# Array.net
KiCad netlist of a schematic drawn in Altium Designer
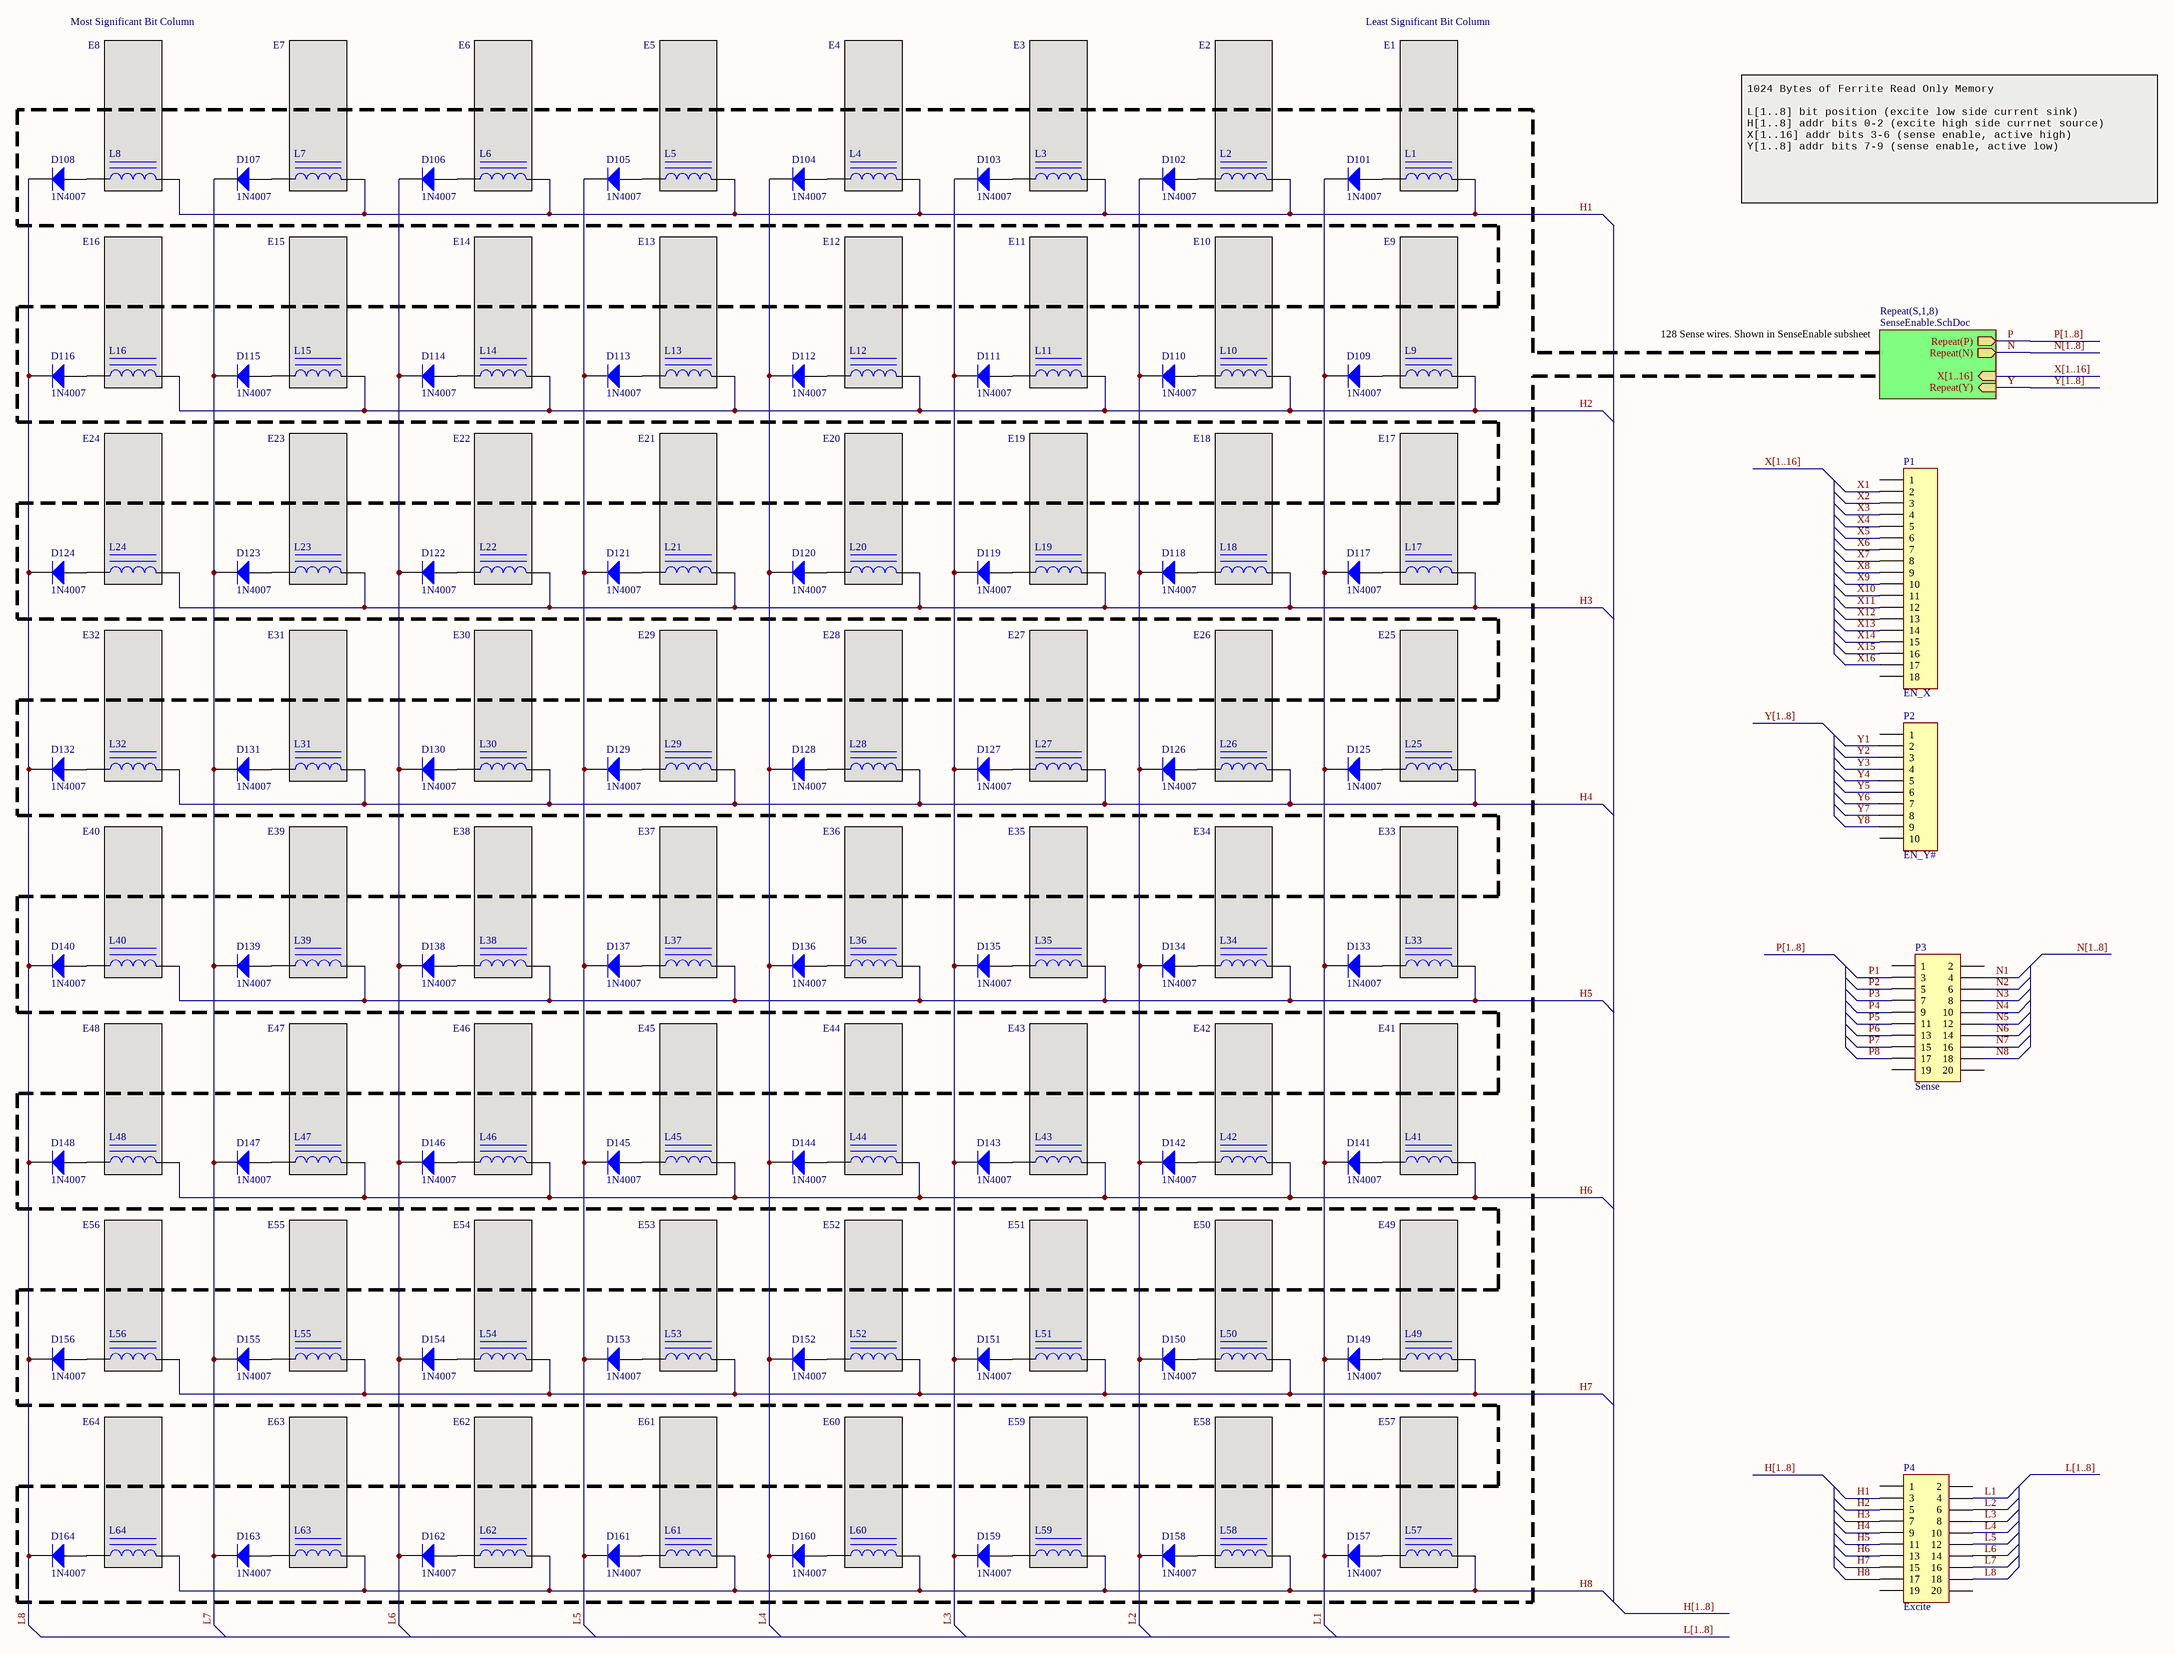
[diagram p0: Array.SchDoc]

(export (version "E")
  (design (tool "Eeschema 10.0.6"))
  (components
    (comp (ref "D101")
      (value "1N4007")
      (footprint "DO-41")
      (description "1 Amp General Purpose Rectifier")
      (fields (field (name "PUBLISHER") "Altium Limited"))
      (libsource (lib "Miscellaneous Devices") (part "Diode 1N4007"))
    )
    (comp (ref "D102")
      (value "1N4007")
      (footprint "DO-41")
      (description "1 Amp General Purpose Rectifier")
      (fields (field (name "PUBLISHER") "Altium Limited"))
      (libsource (lib "Miscellaneous Devices") (part "Diode 1N4007"))
    )
    (comp (ref "D103")
      (value "1N4007")
      (footprint "DO-41")
      (description "1 Amp General Purpose Rectifier")
      (fields (field (name "PUBLISHER") "Altium Limited"))
      (libsource (lib "Miscellaneous Devices") (part "Diode 1N4007"))
    )
    (comp (ref "D104")
      (value "1N4007")
      (footprint "DO-41")
      (description "1 Amp General Purpose Rectifier")
      (fields (field (name "PUBLISHER") "Altium Limited"))
      (libsource (lib "Miscellaneous Devices") (part "Diode 1N4007"))
    )
    (comp (ref "D105")
      (value "1N4007")
      (footprint "DO-41")
      (description "1 Amp General Purpose Rectifier")
      (fields (field (name "PUBLISHER") "Altium Limited"))
      (libsource (lib "Miscellaneous Devices") (part "Diode 1N4007"))
    )
    (comp (ref "D106")
      (value "1N4007")
      (footprint "DO-41")
      (description "1 Amp General Purpose Rectifier")
      (fields (field (name "PUBLISHER") "Altium Limited"))
      (libsource (lib "Miscellaneous Devices") (part "Diode 1N4007"))
    )
    (comp (ref "D107")
      (value "1N4007")
      (footprint "DO-41")
      (description "1 Amp General Purpose Rectifier")
      (fields (field (name "PUBLISHER") "Altium Limited"))
      (libsource (lib "Miscellaneous Devices") (part "Diode 1N4007"))
    )
    (comp (ref "D108")
      (value "1N4007")
      (footprint "DO-41")
      (description "1 Amp General Purpose Rectifier")
      (fields (field (name "PUBLISHER") "Altium Limited"))
      (libsource (lib "Miscellaneous Devices") (part "Diode 1N4007"))
    )
    (comp (ref "D109")
      (value "1N4007")
      (footprint "DO-41")
      (description "1 Amp General Purpose Rectifier")
      (fields (field (name "PUBLISHER") "Altium Limited"))
      (libsource (lib "Miscellaneous Devices") (part "Diode 1N4007"))
    )
    (comp (ref "D110")
      (value "1N4007")
      (footprint "DO-41")
      (description "1 Amp General Purpose Rectifier")
      (fields (field (name "PUBLISHER") "Altium Limited"))
      (libsource (lib "Miscellaneous Devices") (part "Diode 1N4007"))
    )
    (comp (ref "D111")
      (value "1N4007")
      (footprint "DO-41")
      (description "1 Amp General Purpose Rectifier")
      (fields (field (name "PUBLISHER") "Altium Limited"))
      (libsource (lib "Miscellaneous Devices") (part "Diode 1N4007"))
    )
    (comp (ref "D112")
      (value "1N4007")
      (footprint "DO-41")
      (description "1 Amp General Purpose Rectifier")
      (fields (field (name "PUBLISHER") "Altium Limited"))
      (libsource (lib "Miscellaneous Devices") (part "Diode 1N4007"))
    )
    (comp (ref "D113")
      (value "1N4007")
      (footprint "DO-41")
      (description "1 Amp General Purpose Rectifier")
      (fields (field (name "PUBLISHER") "Altium Limited"))
      (libsource (lib "Miscellaneous Devices") (part "Diode 1N4007"))
    )
    (comp (ref "D114")
      (value "1N4007")
      (footprint "DO-41")
      (description "1 Amp General Purpose Rectifier")
      (fields (field (name "PUBLISHER") "Altium Limited"))
      (libsource (lib "Miscellaneous Devices") (part "Diode 1N4007"))
    )
    (comp (ref "D115")
      (value "1N4007")
      (footprint "DO-41")
      (description "1 Amp General Purpose Rectifier")
      (fields (field (name "PUBLISHER") "Altium Limited"))
      (libsource (lib "Miscellaneous Devices") (part "Diode 1N4007"))
    )
    (comp (ref "D116")
      (value "1N4007")
      (footprint "DO-41")
      (description "1 Amp General Purpose Rectifier")
      (fields (field (name "PUBLISHER") "Altium Limited"))
      (libsource (lib "Miscellaneous Devices") (part "Diode 1N4007"))
    )
    (comp (ref "D117")
      (value "1N4007")
      (footprint "DO-41")
      (description "1 Amp General Purpose Rectifier")
      (fields (field (name "PUBLISHER") "Altium Limited"))
      (libsource (lib "Miscellaneous Devices") (part "Diode 1N4007"))
    )
    (comp (ref "D118")
      (value "1N4007")
      (footprint "DO-41")
      (description "1 Amp General Purpose Rectifier")
      (fields (field (name "PUBLISHER") "Altium Limited"))
      (libsource (lib "Miscellaneous Devices") (part "Diode 1N4007"))
    )
    (comp (ref "D119")
      (value "1N4007")
      (footprint "DO-41")
      (description "1 Amp General Purpose Rectifier")
      (fields (field (name "PUBLISHER") "Altium Limited"))
      (libsource (lib "Miscellaneous Devices") (part "Diode 1N4007"))
    )
    (comp (ref "D120")
      (value "1N4007")
      (footprint "DO-41")
      (description "1 Amp General Purpose Rectifier")
      (fields (field (name "PUBLISHER") "Altium Limited"))
      (libsource (lib "Miscellaneous Devices") (part "Diode 1N4007"))
    )
    (comp (ref "D121")
      (value "1N4007")
      (footprint "DO-41")
      (description "1 Amp General Purpose Rectifier")
      (fields (field (name "PUBLISHER") "Altium Limited"))
      (libsource (lib "Miscellaneous Devices") (part "Diode 1N4007"))
    )
    (comp (ref "D122")
      (value "1N4007")
      (footprint "DO-41")
      (description "1 Amp General Purpose Rectifier")
      (fields (field (name "PUBLISHER") "Altium Limited"))
      (libsource (lib "Miscellaneous Devices") (part "Diode 1N4007"))
    )
    (comp (ref "D123")
      (value "1N4007")
      (footprint "DO-41")
      (description "1 Amp General Purpose Rectifier")
      (fields (field (name "PUBLISHER") "Altium Limited"))
      (libsource (lib "Miscellaneous Devices") (part "Diode 1N4007"))
    )
    (comp (ref "D124")
      (value "1N4007")
      (footprint "DO-41")
      (description "1 Amp General Purpose Rectifier")
      (fields (field (name "PUBLISHER") "Altium Limited"))
      (libsource (lib "Miscellaneous Devices") (part "Diode 1N4007"))
    )
    (comp (ref "D125")
      (value "1N4007")
      (footprint "DO-41")
      (description "1 Amp General Purpose Rectifier")
      (fields (field (name "PUBLISHER") "Altium Limited"))
      (libsource (lib "Miscellaneous Devices") (part "Diode 1N4007"))
    )
    (comp (ref "D126")
      (value "1N4007")
      (footprint "DO-41")
      (description "1 Amp General Purpose Rectifier")
      (fields (field (name "PUBLISHER") "Altium Limited"))
      (libsource (lib "Miscellaneous Devices") (part "Diode 1N4007"))
    )
    (comp (ref "D127")
      (value "1N4007")
      (footprint "DO-41")
      (description "1 Amp General Purpose Rectifier")
      (fields (field (name "PUBLISHER") "Altium Limited"))
      (libsource (lib "Miscellaneous Devices") (part "Diode 1N4007"))
    )
    (comp (ref "D128")
      (value "1N4007")
      (footprint "DO-41")
      (description "1 Amp General Purpose Rectifier")
      (fields (field (name "PUBLISHER") "Altium Limited"))
      (libsource (lib "Miscellaneous Devices") (part "Diode 1N4007"))
    )
    (comp (ref "D129")
      (value "1N4007")
      (footprint "DO-41")
      (description "1 Amp General Purpose Rectifier")
      (fields (field (name "PUBLISHER") "Altium Limited"))
      (libsource (lib "Miscellaneous Devices") (part "Diode 1N4007"))
    )
    (comp (ref "D130")
      (value "1N4007")
      (footprint "DO-41")
      (description "1 Amp General Purpose Rectifier")
      (fields (field (name "PUBLISHER") "Altium Limited"))
      (libsource (lib "Miscellaneous Devices") (part "Diode 1N4007"))
    )
    (comp (ref "D131")
      (value "1N4007")
      (footprint "DO-41")
      (description "1 Amp General Purpose Rectifier")
      (fields (field (name "PUBLISHER") "Altium Limited"))
      (libsource (lib "Miscellaneous Devices") (part "Diode 1N4007"))
    )
    (comp (ref "D132")
      (value "1N4007")
      (footprint "DO-41")
      (description "1 Amp General Purpose Rectifier")
      (fields (field (name "PUBLISHER") "Altium Limited"))
      (libsource (lib "Miscellaneous Devices") (part "Diode 1N4007"))
    )
    (comp (ref "D133")
      (value "1N4007")
      (footprint "DO-41")
      (description "1 Amp General Purpose Rectifier")
      (fields (field (name "PUBLISHER") "Altium Limited"))
      (libsource (lib "Miscellaneous Devices") (part "Diode 1N4007"))
    )
    (comp (ref "D134")
      (value "1N4007")
      (footprint "DO-41")
      (description "1 Amp General Purpose Rectifier")
      (fields (field (name "PUBLISHER") "Altium Limited"))
      (libsource (lib "Miscellaneous Devices") (part "Diode 1N4007"))
    )
    (comp (ref "D135")
      (value "1N4007")
      (footprint "DO-41")
      (description "1 Amp General Purpose Rectifier")
      (fields (field (name "PUBLISHER") "Altium Limited"))
      (libsource (lib "Miscellaneous Devices") (part "Diode 1N4007"))
    )
    (comp (ref "D136")
      (value "1N4007")
      (footprint "DO-41")
      (description "1 Amp General Purpose Rectifier")
      (fields (field (name "PUBLISHER") "Altium Limited"))
      (libsource (lib "Miscellaneous Devices") (part "Diode 1N4007"))
    )
    (comp (ref "D137")
      (value "1N4007")
      (footprint "DO-41")
      (description "1 Amp General Purpose Rectifier")
      (fields (field (name "PUBLISHER") "Altium Limited"))
      (libsource (lib "Miscellaneous Devices") (part "Diode 1N4007"))
    )
    (comp (ref "D138")
      (value "1N4007")
      (footprint "DO-41")
      (description "1 Amp General Purpose Rectifier")
      (fields (field (name "PUBLISHER") "Altium Limited"))
      (libsource (lib "Miscellaneous Devices") (part "Diode 1N4007"))
    )
    (comp (ref "D139")
      (value "1N4007")
      (footprint "DO-41")
      (description "1 Amp General Purpose Rectifier")
      (fields (field (name "PUBLISHER") "Altium Limited"))
      (libsource (lib "Miscellaneous Devices") (part "Diode 1N4007"))
    )
    (comp (ref "D140")
      (value "1N4007")
      (footprint "DO-41")
      (description "1 Amp General Purpose Rectifier")
      (fields (field (name "PUBLISHER") "Altium Limited"))
      (libsource (lib "Miscellaneous Devices") (part "Diode 1N4007"))
    )
    (comp (ref "D141")
      (value "1N4007")
      (footprint "DO-41")
      (description "1 Amp General Purpose Rectifier")
      (fields (field (name "PUBLISHER") "Altium Limited"))
      (libsource (lib "Miscellaneous Devices") (part "Diode 1N4007"))
    )
    (comp (ref "D142")
      (value "1N4007")
      (footprint "DO-41")
      (description "1 Amp General Purpose Rectifier")
      (fields (field (name "PUBLISHER") "Altium Limited"))
      (libsource (lib "Miscellaneous Devices") (part "Diode 1N4007"))
    )
    (comp (ref "D143")
      (value "1N4007")
      (footprint "DO-41")
      (description "1 Amp General Purpose Rectifier")
      (fields (field (name "PUBLISHER") "Altium Limited"))
      (libsource (lib "Miscellaneous Devices") (part "Diode 1N4007"))
    )
    (comp (ref "D144")
      (value "1N4007")
      (footprint "DO-41")
      (description "1 Amp General Purpose Rectifier")
      (fields (field (name "PUBLISHER") "Altium Limited"))
      (libsource (lib "Miscellaneous Devices") (part "Diode 1N4007"))
    )
    (comp (ref "D145")
      (value "1N4007")
      (footprint "DO-41")
      (description "1 Amp General Purpose Rectifier")
      (fields (field (name "PUBLISHER") "Altium Limited"))
      (libsource (lib "Miscellaneous Devices") (part "Diode 1N4007"))
    )
    (comp (ref "D146")
      (value "1N4007")
      (footprint "DO-41")
      (description "1 Amp General Purpose Rectifier")
      (fields (field (name "PUBLISHER") "Altium Limited"))
      (libsource (lib "Miscellaneous Devices") (part "Diode 1N4007"))
    )
    (comp (ref "D147")
      (value "1N4007")
      (footprint "DO-41")
      (description "1 Amp General Purpose Rectifier")
      (fields (field (name "PUBLISHER") "Altium Limited"))
      (libsource (lib "Miscellaneous Devices") (part "Diode 1N4007"))
    )
    (comp (ref "D148")
      (value "1N4007")
      (footprint "DO-41")
      (description "1 Amp General Purpose Rectifier")
      (fields (field (name "PUBLISHER") "Altium Limited"))
      (libsource (lib "Miscellaneous Devices") (part "Diode 1N4007"))
    )
    (comp (ref "D149")
      (value "1N4007")
      (footprint "DO-41")
      (description "1 Amp General Purpose Rectifier")
      (fields (field (name "PUBLISHER") "Altium Limited"))
      (libsource (lib "Miscellaneous Devices") (part "Diode 1N4007"))
    )
    (comp (ref "D150")
      (value "1N4007")
      (footprint "DO-41")
      (description "1 Amp General Purpose Rectifier")
      (fields (field (name "PUBLISHER") "Altium Limited"))
      (libsource (lib "Miscellaneous Devices") (part "Diode 1N4007"))
    )
    (comp (ref "D151")
      (value "1N4007")
      (footprint "DO-41")
      (description "1 Amp General Purpose Rectifier")
      (fields (field (name "PUBLISHER") "Altium Limited"))
      (libsource (lib "Miscellaneous Devices") (part "Diode 1N4007"))
    )
    (comp (ref "D152")
      (value "1N4007")
      (footprint "DO-41")
      (description "1 Amp General Purpose Rectifier")
      (fields (field (name "PUBLISHER") "Altium Limited"))
      (libsource (lib "Miscellaneous Devices") (part "Diode 1N4007"))
    )
    (comp (ref "D153")
      (value "1N4007")
      (footprint "DO-41")
      (description "1 Amp General Purpose Rectifier")
      (fields (field (name "PUBLISHER") "Altium Limited"))
      (libsource (lib "Miscellaneous Devices") (part "Diode 1N4007"))
    )
    (comp (ref "D154")
      (value "1N4007")
      (footprint "DO-41")
      (description "1 Amp General Purpose Rectifier")
      (fields (field (name "PUBLISHER") "Altium Limited"))
      (libsource (lib "Miscellaneous Devices") (part "Diode 1N4007"))
    )
    (comp (ref "D155")
      (value "1N4007")
      (footprint "DO-41")
      (description "1 Amp General Purpose Rectifier")
      (fields (field (name "PUBLISHER") "Altium Limited"))
      (libsource (lib "Miscellaneous Devices") (part "Diode 1N4007"))
    )
    (comp (ref "D156")
      (value "1N4007")
      (footprint "DO-41")
      (description "1 Amp General Purpose Rectifier")
      (fields (field (name "PUBLISHER") "Altium Limited"))
      (libsource (lib "Miscellaneous Devices") (part "Diode 1N4007"))
    )
    (comp (ref "D157")
      (value "1N4007")
      (footprint "DO-41")
      (description "1 Amp General Purpose Rectifier")
      (fields (field (name "PUBLISHER") "Altium Limited"))
      (libsource (lib "Miscellaneous Devices") (part "Diode 1N4007"))
    )
    (comp (ref "D158")
      (value "1N4007")
      (footprint "DO-41")
      (description "1 Amp General Purpose Rectifier")
      (fields (field (name "PUBLISHER") "Altium Limited"))
      (libsource (lib "Miscellaneous Devices") (part "Diode 1N4007"))
    )
    (comp (ref "D159")
      (value "1N4007")
      (footprint "DO-41")
      (description "1 Amp General Purpose Rectifier")
      (fields (field (name "PUBLISHER") "Altium Limited"))
      (libsource (lib "Miscellaneous Devices") (part "Diode 1N4007"))
    )
    (comp (ref "D160")
      (value "1N4007")
      (footprint "DO-41")
      (description "1 Amp General Purpose Rectifier")
      (fields (field (name "PUBLISHER") "Altium Limited"))
      (libsource (lib "Miscellaneous Devices") (part "Diode 1N4007"))
    )
    (comp (ref "D161")
      (value "1N4007")
      (footprint "DO-41")
      (description "1 Amp General Purpose Rectifier")
      (fields (field (name "PUBLISHER") "Altium Limited"))
      (libsource (lib "Miscellaneous Devices") (part "Diode 1N4007"))
    )
    (comp (ref "D162")
      (value "1N4007")
      (footprint "DO-41")
      (description "1 Amp General Purpose Rectifier")
      (fields (field (name "PUBLISHER") "Altium Limited"))
      (libsource (lib "Miscellaneous Devices") (part "Diode 1N4007"))
    )
    (comp (ref "D163")
      (value "1N4007")
      (footprint "DO-41")
      (description "1 Amp General Purpose Rectifier")
      (fields (field (name "PUBLISHER") "Altium Limited"))
      (libsource (lib "Miscellaneous Devices") (part "Diode 1N4007"))
    )
    (comp (ref "D164")
      (value "1N4007")
      (footprint "DO-41")
      (description "1 Amp General Purpose Rectifier")
      (fields (field (name "PUBLISHER") "Altium Limited"))
      (libsource (lib "Miscellaneous Devices") (part "Diode 1N4007"))
    )
    (comp (ref "L1")
      (value "Inductor Iron")
      (footprint "AXIAL-0.9")
      (description "Magnetic-Core Inductor")
      (fields (field (name "PUBLISHER") "Altium Limited"))
      (libsource (lib "Miscellaneous Devices") (part "Inductor Iron"))
    )
    (comp (ref "L2")
      (value "Inductor Iron")
      (footprint "AXIAL-0.9")
      (description "Magnetic-Core Inductor")
      (fields (field (name "PUBLISHER") "Altium Limited"))
      (libsource (lib "Miscellaneous Devices") (part "Inductor Iron"))
    )
    (comp (ref "L3")
      (value "Inductor Iron")
      (footprint "AXIAL-0.9")
      (description "Magnetic-Core Inductor")
      (fields (field (name "PUBLISHER") "Altium Limited"))
      (libsource (lib "Miscellaneous Devices") (part "Inductor Iron"))
    )
    (comp (ref "L4")
      (value "Inductor Iron")
      (footprint "AXIAL-0.9")
      (description "Magnetic-Core Inductor")
      (fields (field (name "PUBLISHER") "Altium Limited"))
      (libsource (lib "Miscellaneous Devices") (part "Inductor Iron"))
    )
    (comp (ref "L5")
      (value "Inductor Iron")
      (footprint "AXIAL-0.9")
      (description "Magnetic-Core Inductor")
      (fields (field (name "PUBLISHER") "Altium Limited"))
      (libsource (lib "Miscellaneous Devices") (part "Inductor Iron"))
    )
    (comp (ref "L6")
      (value "Inductor Iron")
      (footprint "AXIAL-0.9")
      (description "Magnetic-Core Inductor")
      (fields (field (name "PUBLISHER") "Altium Limited"))
      (libsource (lib "Miscellaneous Devices") (part "Inductor Iron"))
    )
    (comp (ref "L7")
      (value "Inductor Iron")
      (footprint "AXIAL-0.9")
      (description "Magnetic-Core Inductor")
      (fields (field (name "PUBLISHER") "Altium Limited"))
      (libsource (lib "Miscellaneous Devices") (part "Inductor Iron"))
    )
    (comp (ref "L8")
      (value "Inductor Iron")
      (footprint "AXIAL-0.9")
      (description "Magnetic-Core Inductor")
      (fields (field (name "PUBLISHER") "Altium Limited"))
      (libsource (lib "Miscellaneous Devices") (part "Inductor Iron"))
    )
    (comp (ref "L9")
      (value "Inductor Iron")
      (footprint "AXIAL-0.9")
      (description "Magnetic-Core Inductor")
      (fields (field (name "PUBLISHER") "Altium Limited"))
      (libsource (lib "Miscellaneous Devices") (part "Inductor Iron"))
    )
    (comp (ref "L10")
      (value "Inductor Iron")
      (footprint "AXIAL-0.9")
      (description "Magnetic-Core Inductor")
      (fields (field (name "PUBLISHER") "Altium Limited"))
      (libsource (lib "Miscellaneous Devices") (part "Inductor Iron"))
    )
    (comp (ref "L11")
      (value "Inductor Iron")
      (footprint "AXIAL-0.9")
      (description "Magnetic-Core Inductor")
      (fields (field (name "PUBLISHER") "Altium Limited"))
      (libsource (lib "Miscellaneous Devices") (part "Inductor Iron"))
    )
    (comp (ref "L12")
      (value "Inductor Iron")
      (footprint "AXIAL-0.9")
      (description "Magnetic-Core Inductor")
      (fields (field (name "PUBLISHER") "Altium Limited"))
      (libsource (lib "Miscellaneous Devices") (part "Inductor Iron"))
    )
    (comp (ref "L13")
      (value "Inductor Iron")
      (footprint "AXIAL-0.9")
      (description "Magnetic-Core Inductor")
      (fields (field (name "PUBLISHER") "Altium Limited"))
      (libsource (lib "Miscellaneous Devices") (part "Inductor Iron"))
    )
    (comp (ref "L14")
      (value "Inductor Iron")
      (footprint "AXIAL-0.9")
      (description "Magnetic-Core Inductor")
      (fields (field (name "PUBLISHER") "Altium Limited"))
      (libsource (lib "Miscellaneous Devices") (part "Inductor Iron"))
    )
    (comp (ref "L15")
      (value "Inductor Iron")
      (footprint "AXIAL-0.9")
      (description "Magnetic-Core Inductor")
      (fields (field (name "PUBLISHER") "Altium Limited"))
      (libsource (lib "Miscellaneous Devices") (part "Inductor Iron"))
    )
    (comp (ref "L16")
      (value "Inductor Iron")
      (footprint "AXIAL-0.9")
      (description "Magnetic-Core Inductor")
      (fields (field (name "PUBLISHER") "Altium Limited"))
      (libsource (lib "Miscellaneous Devices") (part "Inductor Iron"))
    )
    (comp (ref "L17")
      (value "Inductor Iron")
      (footprint "AXIAL-0.9")
      (description "Magnetic-Core Inductor")
      (fields (field (name "PUBLISHER") "Altium Limited"))
      (libsource (lib "Miscellaneous Devices") (part "Inductor Iron"))
    )
    (comp (ref "L18")
      (value "Inductor Iron")
      (footprint "AXIAL-0.9")
      (description "Magnetic-Core Inductor")
      (fields (field (name "PUBLISHER") "Altium Limited"))
      (libsource (lib "Miscellaneous Devices") (part "Inductor Iron"))
    )
    (comp (ref "L19")
      (value "Inductor Iron")
      (footprint "AXIAL-0.9")
      (description "Magnetic-Core Inductor")
      (fields (field (name "PUBLISHER") "Altium Limited"))
      (libsource (lib "Miscellaneous Devices") (part "Inductor Iron"))
    )
    (comp (ref "L20")
      (value "Inductor Iron")
      (footprint "AXIAL-0.9")
      (description "Magnetic-Core Inductor")
      (fields (field (name "PUBLISHER") "Altium Limited"))
      (libsource (lib "Miscellaneous Devices") (part "Inductor Iron"))
    )
    (comp (ref "L21")
      (value "Inductor Iron")
      (footprint "AXIAL-0.9")
      (description "Magnetic-Core Inductor")
      (fields (field (name "PUBLISHER") "Altium Limited"))
      (libsource (lib "Miscellaneous Devices") (part "Inductor Iron"))
    )
    (comp (ref "L22")
      (value "Inductor Iron")
      (footprint "AXIAL-0.9")
      (description "Magnetic-Core Inductor")
      (fields (field (name "PUBLISHER") "Altium Limited"))
      (libsource (lib "Miscellaneous Devices") (part "Inductor Iron"))
    )
    (comp (ref "L23")
      (value "Inductor Iron")
      (footprint "AXIAL-0.9")
      (description "Magnetic-Core Inductor")
      (fields (field (name "PUBLISHER") "Altium Limited"))
      (libsource (lib "Miscellaneous Devices") (part "Inductor Iron"))
    )
    (comp (ref "L24")
      (value "Inductor Iron")
      (footprint "AXIAL-0.9")
      (description "Magnetic-Core Inductor")
      (fields (field (name "PUBLISHER") "Altium Limited"))
      (libsource (lib "Miscellaneous Devices") (part "Inductor Iron"))
    )
    (comp (ref "L25")
      (value "Inductor Iron")
      (footprint "AXIAL-0.9")
      (description "Magnetic-Core Inductor")
      (fields (field (name "PUBLISHER") "Altium Limited"))
      (libsource (lib "Miscellaneous Devices") (part "Inductor Iron"))
    )
    (comp (ref "L26")
      (value "Inductor Iron")
      (footprint "AXIAL-0.9")
      (description "Magnetic-Core Inductor")
      (fields (field (name "PUBLISHER") "Altium Limited"))
      (libsource (lib "Miscellaneous Devices") (part "Inductor Iron"))
    )
    (comp (ref "L27")
      (value "Inductor Iron")
      (footprint "AXIAL-0.9")
      (description "Magnetic-Core Inductor")
      (fields (field (name "PUBLISHER") "Altium Limited"))
      (libsource (lib "Miscellaneous Devices") (part "Inductor Iron"))
    )
    (comp (ref "L28")
      (value "Inductor Iron")
      (footprint "AXIAL-0.9")
      (description "Magnetic-Core Inductor")
      (fields (field (name "PUBLISHER") "Altium Limited"))
      (libsource (lib "Miscellaneous Devices") (part "Inductor Iron"))
    )
    (comp (ref "L29")
      (value "Inductor Iron")
      (footprint "AXIAL-0.9")
      (description "Magnetic-Core Inductor")
      (fields (field (name "PUBLISHER") "Altium Limited"))
      (libsource (lib "Miscellaneous Devices") (part "Inductor Iron"))
    )
    (comp (ref "L30")
      (value "Inductor Iron")
      (footprint "AXIAL-0.9")
      (description "Magnetic-Core Inductor")
      (fields (field (name "PUBLISHER") "Altium Limited"))
      (libsource (lib "Miscellaneous Devices") (part "Inductor Iron"))
    )
    (comp (ref "L31")
      (value "Inductor Iron")
      (footprint "AXIAL-0.9")
      (description "Magnetic-Core Inductor")
      (fields (field (name "PUBLISHER") "Altium Limited"))
      (libsource (lib "Miscellaneous Devices") (part "Inductor Iron"))
    )
    (comp (ref "L32")
      (value "Inductor Iron")
      (footprint "AXIAL-0.9")
      (description "Magnetic-Core Inductor")
      (fields (field (name "PUBLISHER") "Altium Limited"))
      (libsource (lib "Miscellaneous Devices") (part "Inductor Iron"))
    )
    (comp (ref "L33")
      (value "Inductor Iron")
      (footprint "AXIAL-0.9")
      (description "Magnetic-Core Inductor")
      (fields (field (name "PUBLISHER") "Altium Limited"))
      (libsource (lib "Miscellaneous Devices") (part "Inductor Iron"))
    )
    (comp (ref "L34")
      (value "Inductor Iron")
      (footprint "AXIAL-0.9")
      (description "Magnetic-Core Inductor")
      (fields (field (name "PUBLISHER") "Altium Limited"))
      (libsource (lib "Miscellaneous Devices") (part "Inductor Iron"))
    )
    (comp (ref "L35")
      (value "Inductor Iron")
      (footprint "AXIAL-0.9")
      (description "Magnetic-Core Inductor")
      (fields (field (name "PUBLISHER") "Altium Limited"))
      (libsource (lib "Miscellaneous Devices") (part "Inductor Iron"))
    )
    (comp (ref "L36")
      (value "Inductor Iron")
      (footprint "AXIAL-0.9")
      (description "Magnetic-Core Inductor")
      (fields (field (name "PUBLISHER") "Altium Limited"))
      (libsource (lib "Miscellaneous Devices") (part "Inductor Iron"))
    )
    (comp (ref "L37")
      (value "Inductor Iron")
      (footprint "AXIAL-0.9")
      (description "Magnetic-Core Inductor")
      (fields (field (name "PUBLISHER") "Altium Limited"))
      (libsource (lib "Miscellaneous Devices") (part "Inductor Iron"))
    )
    (comp (ref "L38")
      (value "Inductor Iron")
      (footprint "AXIAL-0.9")
      (description "Magnetic-Core Inductor")
      (fields (field (name "PUBLISHER") "Altium Limited"))
      (libsource (lib "Miscellaneous Devices") (part "Inductor Iron"))
    )
    (comp (ref "L39")
      (value "Inductor Iron")
      (footprint "AXIAL-0.9")
      (description "Magnetic-Core Inductor")
      (fields (field (name "PUBLISHER") "Altium Limited"))
      (libsource (lib "Miscellaneous Devices") (part "Inductor Iron"))
    )
    (comp (ref "L40")
      (value "Inductor Iron")
      (footprint "AXIAL-0.9")
      (description "Magnetic-Core Inductor")
      (fields (field (name "PUBLISHER") "Altium Limited"))
      (libsource (lib "Miscellaneous Devices") (part "Inductor Iron"))
    )
    (comp (ref "L41")
      (value "Inductor Iron")
      (footprint "AXIAL-0.9")
      (description "Magnetic-Core Inductor")
      (fields (field (name "PUBLISHER") "Altium Limited"))
      (libsource (lib "Miscellaneous Devices") (part "Inductor Iron"))
    )
    (comp (ref "L42")
      (value "Inductor Iron")
      (footprint "AXIAL-0.9")
      (description "Magnetic-Core Inductor")
      (fields (field (name "PUBLISHER") "Altium Limited"))
      (libsource (lib "Miscellaneous Devices") (part "Inductor Iron"))
    )
    (comp (ref "L43")
      (value "Inductor Iron")
      (footprint "AXIAL-0.9")
      (description "Magnetic-Core Inductor")
      (fields (field (name "PUBLISHER") "Altium Limited"))
      (libsource (lib "Miscellaneous Devices") (part "Inductor Iron"))
    )
    (comp (ref "L44")
      (value "Inductor Iron")
      (footprint "AXIAL-0.9")
      (description "Magnetic-Core Inductor")
      (fields (field (name "PUBLISHER") "Altium Limited"))
      (libsource (lib "Miscellaneous Devices") (part "Inductor Iron"))
    )
    (comp (ref "L45")
      (value "Inductor Iron")
      (footprint "AXIAL-0.9")
      (description "Magnetic-Core Inductor")
      (fields (field (name "PUBLISHER") "Altium Limited"))
      (libsource (lib "Miscellaneous Devices") (part "Inductor Iron"))
    )
    (comp (ref "L46")
      (value "Inductor Iron")
      (footprint "AXIAL-0.9")
      (description "Magnetic-Core Inductor")
      (fields (field (name "PUBLISHER") "Altium Limited"))
      (libsource (lib "Miscellaneous Devices") (part "Inductor Iron"))
    )
    (comp (ref "L47")
      (value "Inductor Iron")
      (footprint "AXIAL-0.9")
      (description "Magnetic-Core Inductor")
      (fields (field (name "PUBLISHER") "Altium Limited"))
      (libsource (lib "Miscellaneous Devices") (part "Inductor Iron"))
    )
    (comp (ref "L48")
      (value "Inductor Iron")
      (footprint "AXIAL-0.9")
      (description "Magnetic-Core Inductor")
      (fields (field (name "PUBLISHER") "Altium Limited"))
      (libsource (lib "Miscellaneous Devices") (part "Inductor Iron"))
    )
    (comp (ref "L49")
      (value "Inductor Iron")
      (footprint "AXIAL-0.9")
      (description "Magnetic-Core Inductor")
      (fields (field (name "PUBLISHER") "Altium Limited"))
      (libsource (lib "Miscellaneous Devices") (part "Inductor Iron"))
    )
    (comp (ref "L50")
      (value "Inductor Iron")
      (footprint "AXIAL-0.9")
      (description "Magnetic-Core Inductor")
      (fields (field (name "PUBLISHER") "Altium Limited"))
      (libsource (lib "Miscellaneous Devices") (part "Inductor Iron"))
    )
    (comp (ref "L51")
      (value "Inductor Iron")
      (footprint "AXIAL-0.9")
      (description "Magnetic-Core Inductor")
      (fields (field (name "PUBLISHER") "Altium Limited"))
      (libsource (lib "Miscellaneous Devices") (part "Inductor Iron"))
    )
    (comp (ref "L52")
      (value "Inductor Iron")
      (footprint "AXIAL-0.9")
      (description "Magnetic-Core Inductor")
      (fields (field (name "PUBLISHER") "Altium Limited"))
      (libsource (lib "Miscellaneous Devices") (part "Inductor Iron"))
    )
    (comp (ref "L53")
      (value "Inductor Iron")
      (footprint "AXIAL-0.9")
      (description "Magnetic-Core Inductor")
      (fields (field (name "PUBLISHER") "Altium Limited"))
      (libsource (lib "Miscellaneous Devices") (part "Inductor Iron"))
    )
    (comp (ref "L54")
      (value "Inductor Iron")
      (footprint "AXIAL-0.9")
      (description "Magnetic-Core Inductor")
      (fields (field (name "PUBLISHER") "Altium Limited"))
      (libsource (lib "Miscellaneous Devices") (part "Inductor Iron"))
    )
    (comp (ref "L55")
      (value "Inductor Iron")
      (footprint "AXIAL-0.9")
      (description "Magnetic-Core Inductor")
      (fields (field (name "PUBLISHER") "Altium Limited"))
      (libsource (lib "Miscellaneous Devices") (part "Inductor Iron"))
    )
    (comp (ref "L56")
      (value "Inductor Iron")
      (footprint "AXIAL-0.9")
      (description "Magnetic-Core Inductor")
      (fields (field (name "PUBLISHER") "Altium Limited"))
      (libsource (lib "Miscellaneous Devices") (part "Inductor Iron"))
    )
    (comp (ref "L57")
      (value "Inductor Iron")
      (footprint "AXIAL-0.9")
      (description "Magnetic-Core Inductor")
      (fields (field (name "PUBLISHER") "Altium Limited"))
      (libsource (lib "Miscellaneous Devices") (part "Inductor Iron"))
    )
    (comp (ref "L58")
      (value "Inductor Iron")
      (footprint "AXIAL-0.9")
      (description "Magnetic-Core Inductor")
      (fields (field (name "PUBLISHER") "Altium Limited"))
      (libsource (lib "Miscellaneous Devices") (part "Inductor Iron"))
    )
    (comp (ref "L59")
      (value "Inductor Iron")
      (footprint "AXIAL-0.9")
      (description "Magnetic-Core Inductor")
      (fields (field (name "PUBLISHER") "Altium Limited"))
      (libsource (lib "Miscellaneous Devices") (part "Inductor Iron"))
    )
    (comp (ref "L60")
      (value "Inductor Iron")
      (footprint "AXIAL-0.9")
      (description "Magnetic-Core Inductor")
      (fields (field (name "PUBLISHER") "Altium Limited"))
      (libsource (lib "Miscellaneous Devices") (part "Inductor Iron"))
    )
    (comp (ref "L61")
      (value "Inductor Iron")
      (footprint "AXIAL-0.9")
      (description "Magnetic-Core Inductor")
      (fields (field (name "PUBLISHER") "Altium Limited"))
      (libsource (lib "Miscellaneous Devices") (part "Inductor Iron"))
    )
    (comp (ref "L62")
      (value "Inductor Iron")
      (footprint "AXIAL-0.9")
      (description "Magnetic-Core Inductor")
      (fields (field (name "PUBLISHER") "Altium Limited"))
      (libsource (lib "Miscellaneous Devices") (part "Inductor Iron"))
    )
    (comp (ref "L63")
      (value "Inductor Iron")
      (footprint "AXIAL-0.9")
      (description "Magnetic-Core Inductor")
      (fields (field (name "PUBLISHER") "Altium Limited"))
      (libsource (lib "Miscellaneous Devices") (part "Inductor Iron"))
    )
    (comp (ref "L64")
      (value "Inductor Iron")
      (footprint "AXIAL-0.9")
      (description "Magnetic-Core Inductor")
      (fields (field (name "PUBLISHER") "Altium Limited"))
      (libsource (lib "Miscellaneous Devices") (part "Inductor Iron"))
    )
    (comp (ref "P1")
      (value "EN_X")
      (footprint "HDR1X18")
      (description "Header, 18-Pin")
      (fields (field (name "PUBLISHER") "Altium Limited"))
      (libsource (lib "Miscellaneous Connectors") (part "Header 18"))
    )
    (comp (ref "P2")
      (value "EN_Y#")
      (footprint "HDR1X10")
      (description "Header, 10-Pin")
      (fields (field (name "PUBLISHER") "Altium Limited"))
      (libsource (lib "Miscellaneous Connectors") (part "Header 10"))
    )
    (comp (ref "P3")
      (value "Sense")
      (footprint "HDR2X10")
      (description "Header, 10-Pin, Dual row")
      (fields (field (name "PUBLISHER") "Altium Limited"))
      (libsource (lib "Miscellaneous Connectors") (part "Header 10X2"))
    )
    (comp (ref "P4")
      (value "Excite")
      (footprint "HDR2X10")
      (description "Header, 10-Pin, Dual row")
      (fields (field (name "PUBLISHER") "Altium Limited"))
      (libsource (lib "Miscellaneous Connectors") (part "Header 10X2"))
    )
  )
  (nets
    (net (code "1") (name "/H1") (class "Default")
      (node (ref "L1") (pin "2") (pinfunction "2_2") (pintype "passive"))
      (node (ref "L2") (pin "2") (pinfunction "2_2") (pintype "passive"))
      (node (ref "L3") (pin "2") (pinfunction "2_2") (pintype "passive"))
      (node (ref "L4") (pin "2") (pinfunction "2_2") (pintype "passive"))
      (node (ref "L5") (pin "2") (pinfunction "2_2") (pintype "passive"))
      (node (ref "L6") (pin "2") (pinfunction "2_2") (pintype "passive"))
      (node (ref "L7") (pin "2") (pinfunction "2_2") (pintype "passive"))
      (node (ref "L8") (pin "2") (pinfunction "2_2") (pintype "passive"))
      (node (ref "P4") (pin "3") (pinfunction "3_3") (pintype "passive"))
    )
    (net (code "2") (name "/H2") (class "Default")
      (node (ref "L10") (pin "2") (pinfunction "2_2") (pintype "passive"))
      (node (ref "L11") (pin "2") (pinfunction "2_2") (pintype "passive"))
      (node (ref "L12") (pin "2") (pinfunction "2_2") (pintype "passive"))
      (node (ref "L13") (pin "2") (pinfunction "2_2") (pintype "passive"))
      (node (ref "L14") (pin "2") (pinfunction "2_2") (pintype "passive"))
      (node (ref "L15") (pin "2") (pinfunction "2_2") (pintype "passive"))
      (node (ref "L16") (pin "2") (pinfunction "2_2") (pintype "passive"))
      (node (ref "L9") (pin "2") (pinfunction "2_2") (pintype "passive"))
      (node (ref "P4") (pin "5") (pinfunction "5_5") (pintype "passive"))
    )
    (net (code "3") (name "/H3") (class "Default")
      (node (ref "L17") (pin "2") (pinfunction "2_2") (pintype "passive"))
      (node (ref "L18") (pin "2") (pinfunction "2_2") (pintype "passive"))
      (node (ref "L19") (pin "2") (pinfunction "2_2") (pintype "passive"))
      (node (ref "L20") (pin "2") (pinfunction "2_2") (pintype "passive"))
      (node (ref "L21") (pin "2") (pinfunction "2_2") (pintype "passive"))
      (node (ref "L22") (pin "2") (pinfunction "2_2") (pintype "passive"))
      (node (ref "L23") (pin "2") (pinfunction "2_2") (pintype "passive"))
      (node (ref "L24") (pin "2") (pinfunction "2_2") (pintype "passive"))
      (node (ref "P4") (pin "7") (pinfunction "7_7") (pintype "passive"))
    )
    (net (code "4") (name "/H4") (class "Default")
      (node (ref "L25") (pin "2") (pinfunction "2_2") (pintype "passive"))
      (node (ref "L26") (pin "2") (pinfunction "2_2") (pintype "passive"))
      (node (ref "L27") (pin "2") (pinfunction "2_2") (pintype "passive"))
      (node (ref "L28") (pin "2") (pinfunction "2_2") (pintype "passive"))
      (node (ref "L29") (pin "2") (pinfunction "2_2") (pintype "passive"))
      (node (ref "L30") (pin "2") (pinfunction "2_2") (pintype "passive"))
      (node (ref "L31") (pin "2") (pinfunction "2_2") (pintype "passive"))
      (node (ref "L32") (pin "2") (pinfunction "2_2") (pintype "passive"))
      (node (ref "P4") (pin "9") (pinfunction "9_9") (pintype "passive"))
    )
    (net (code "5") (name "/H5") (class "Default")
      (node (ref "L33") (pin "2") (pinfunction "2_2") (pintype "passive"))
      (node (ref "L34") (pin "2") (pinfunction "2_2") (pintype "passive"))
      (node (ref "L35") (pin "2") (pinfunction "2_2") (pintype "passive"))
      (node (ref "L36") (pin "2") (pinfunction "2_2") (pintype "passive"))
      (node (ref "L37") (pin "2") (pinfunction "2_2") (pintype "passive"))
      (node (ref "L38") (pin "2") (pinfunction "2_2") (pintype "passive"))
      (node (ref "L39") (pin "2") (pinfunction "2_2") (pintype "passive"))
      (node (ref "L40") (pin "2") (pinfunction "2_2") (pintype "passive"))
      (node (ref "P4") (pin "11") (pinfunction "11_11") (pintype "passive"))
    )
    (net (code "6") (name "/H6") (class "Default")
      (node (ref "L41") (pin "2") (pinfunction "2_2") (pintype "passive"))
      (node (ref "L42") (pin "2") (pinfunction "2_2") (pintype "passive"))
      (node (ref "L43") (pin "2") (pinfunction "2_2") (pintype "passive"))
      (node (ref "L44") (pin "2") (pinfunction "2_2") (pintype "passive"))
      (node (ref "L45") (pin "2") (pinfunction "2_2") (pintype "passive"))
      (node (ref "L46") (pin "2") (pinfunction "2_2") (pintype "passive"))
      (node (ref "L47") (pin "2") (pinfunction "2_2") (pintype "passive"))
      (node (ref "L48") (pin "2") (pinfunction "2_2") (pintype "passive"))
      (node (ref "P4") (pin "13") (pinfunction "13_13") (pintype "passive"))
    )
    (net (code "7") (name "/H7") (class "Default")
      (node (ref "L49") (pin "2") (pinfunction "2_2") (pintype "passive"))
      (node (ref "L50") (pin "2") (pinfunction "2_2") (pintype "passive"))
      (node (ref "L51") (pin "2") (pinfunction "2_2") (pintype "passive"))
      (node (ref "L52") (pin "2") (pinfunction "2_2") (pintype "passive"))
      (node (ref "L53") (pin "2") (pinfunction "2_2") (pintype "passive"))
      (node (ref "L54") (pin "2") (pinfunction "2_2") (pintype "passive"))
      (node (ref "L55") (pin "2") (pinfunction "2_2") (pintype "passive"))
      (node (ref "L56") (pin "2") (pinfunction "2_2") (pintype "passive"))
      (node (ref "P4") (pin "15") (pinfunction "15_15") (pintype "passive"))
    )
    (net (code "8") (name "/H8") (class "Default")
      (node (ref "L57") (pin "2") (pinfunction "2_2") (pintype "passive"))
      (node (ref "L58") (pin "2") (pinfunction "2_2") (pintype "passive"))
      (node (ref "L59") (pin "2") (pinfunction "2_2") (pintype "passive"))
      (node (ref "L60") (pin "2") (pinfunction "2_2") (pintype "passive"))
      (node (ref "L61") (pin "2") (pinfunction "2_2") (pintype "passive"))
      (node (ref "L62") (pin "2") (pinfunction "2_2") (pintype "passive"))
      (node (ref "L63") (pin "2") (pinfunction "2_2") (pintype "passive"))
      (node (ref "L64") (pin "2") (pinfunction "2_2") (pintype "passive"))
      (node (ref "P4") (pin "17") (pinfunction "17_17") (pintype "passive"))
    )
    (net (code "10") (name "/L1") (class "Default")
      (node (ref "D101") (pin "2") (pinfunction "K_2") (pintype "passive"))
      (node (ref "D109") (pin "2") (pinfunction "K_2") (pintype "passive"))
      (node (ref "D117") (pin "2") (pinfunction "K_2") (pintype "passive"))
      (node (ref "D125") (pin "2") (pinfunction "K_2") (pintype "passive"))
      (node (ref "D133") (pin "2") (pinfunction "K_2") (pintype "passive"))
      (node (ref "D141") (pin "2") (pinfunction "K_2") (pintype "passive"))
      (node (ref "D149") (pin "2") (pinfunction "K_2") (pintype "passive"))
      (node (ref "D157") (pin "2") (pinfunction "K_2") (pintype "passive"))
      (node (ref "P4") (pin "4") (pinfunction "4_4") (pintype "passive"))
    )
    (net (code "11") (name "/L2") (class "Default")
      (node (ref "D102") (pin "2") (pinfunction "K_2") (pintype "passive"))
      (node (ref "D110") (pin "2") (pinfunction "K_2") (pintype "passive"))
      (node (ref "D118") (pin "2") (pinfunction "K_2") (pintype "passive"))
      (node (ref "D126") (pin "2") (pinfunction "K_2") (pintype "passive"))
      (node (ref "D134") (pin "2") (pinfunction "K_2") (pintype "passive"))
      (node (ref "D142") (pin "2") (pinfunction "K_2") (pintype "passive"))
      (node (ref "D150") (pin "2") (pinfunction "K_2") (pintype "passive"))
      (node (ref "D158") (pin "2") (pinfunction "K_2") (pintype "passive"))
      (node (ref "P4") (pin "6") (pinfunction "6_6") (pintype "passive"))
    )
    (net (code "12") (name "/L3") (class "Default")
      (node (ref "D103") (pin "2") (pinfunction "K_2") (pintype "passive"))
      (node (ref "D111") (pin "2") (pinfunction "K_2") (pintype "passive"))
      (node (ref "D119") (pin "2") (pinfunction "K_2") (pintype "passive"))
      (node (ref "D127") (pin "2") (pinfunction "K_2") (pintype "passive"))
      (node (ref "D135") (pin "2") (pinfunction "K_2") (pintype "passive"))
      (node (ref "D143") (pin "2") (pinfunction "K_2") (pintype "passive"))
      (node (ref "D151") (pin "2") (pinfunction "K_2") (pintype "passive"))
      (node (ref "D159") (pin "2") (pinfunction "K_2") (pintype "passive"))
      (node (ref "P4") (pin "8") (pinfunction "8_8") (pintype "passive"))
    )
    (net (code "13") (name "/L4") (class "Default")
      (node (ref "D104") (pin "2") (pinfunction "K_2") (pintype "passive"))
      (node (ref "D112") (pin "2") (pinfunction "K_2") (pintype "passive"))
      (node (ref "D120") (pin "2") (pinfunction "K_2") (pintype "passive"))
      (node (ref "D128") (pin "2") (pinfunction "K_2") (pintype "passive"))
      (node (ref "D136") (pin "2") (pinfunction "K_2") (pintype "passive"))
      (node (ref "D144") (pin "2") (pinfunction "K_2") (pintype "passive"))
      (node (ref "D152") (pin "2") (pinfunction "K_2") (pintype "passive"))
      (node (ref "D160") (pin "2") (pinfunction "K_2") (pintype "passive"))
      (node (ref "P4") (pin "10") (pinfunction "10_10") (pintype "passive"))
    )
    (net (code "14") (name "/L5") (class "Default")
      (node (ref "D105") (pin "2") (pinfunction "K_2") (pintype "passive"))
      (node (ref "D113") (pin "2") (pinfunction "K_2") (pintype "passive"))
      (node (ref "D121") (pin "2") (pinfunction "K_2") (pintype "passive"))
      (node (ref "D129") (pin "2") (pinfunction "K_2") (pintype "passive"))
      (node (ref "D137") (pin "2") (pinfunction "K_2") (pintype "passive"))
      (node (ref "D145") (pin "2") (pinfunction "K_2") (pintype "passive"))
      (node (ref "D153") (pin "2") (pinfunction "K_2") (pintype "passive"))
      (node (ref "D161") (pin "2") (pinfunction "K_2") (pintype "passive"))
      (node (ref "P4") (pin "12") (pinfunction "12_12") (pintype "passive"))
    )
    (net (code "15") (name "/L6") (class "Default")
      (node (ref "D106") (pin "2") (pinfunction "K_2") (pintype "passive"))
      (node (ref "D114") (pin "2") (pinfunction "K_2") (pintype "passive"))
      (node (ref "D122") (pin "2") (pinfunction "K_2") (pintype "passive"))
      (node (ref "D130") (pin "2") (pinfunction "K_2") (pintype "passive"))
      (node (ref "D138") (pin "2") (pinfunction "K_2") (pintype "passive"))
      (node (ref "D146") (pin "2") (pinfunction "K_2") (pintype "passive"))
      (node (ref "D154") (pin "2") (pinfunction "K_2") (pintype "passive"))
      (node (ref "D162") (pin "2") (pinfunction "K_2") (pintype "passive"))
      (node (ref "P4") (pin "14") (pinfunction "14_14") (pintype "passive"))
    )
    (net (code "16") (name "/L7") (class "Default")
      (node (ref "D107") (pin "2") (pinfunction "K_2") (pintype "passive"))
      (node (ref "D115") (pin "2") (pinfunction "K_2") (pintype "passive"))
      (node (ref "D123") (pin "2") (pinfunction "K_2") (pintype "passive"))
      (node (ref "D131") (pin "2") (pinfunction "K_2") (pintype "passive"))
      (node (ref "D139") (pin "2") (pinfunction "K_2") (pintype "passive"))
      (node (ref "D147") (pin "2") (pinfunction "K_2") (pintype "passive"))
      (node (ref "D155") (pin "2") (pinfunction "K_2") (pintype "passive"))
      (node (ref "D163") (pin "2") (pinfunction "K_2") (pintype "passive"))
      (node (ref "P4") (pin "16") (pinfunction "16_16") (pintype "passive"))
    )
    (net (code "17") (name "/L8") (class "Default")
      (node (ref "D108") (pin "2") (pinfunction "K_2") (pintype "passive"))
      (node (ref "D116") (pin "2") (pinfunction "K_2") (pintype "passive"))
      (node (ref "D124") (pin "2") (pinfunction "K_2") (pintype "passive"))
      (node (ref "D132") (pin "2") (pinfunction "K_2") (pintype "passive"))
      (node (ref "D140") (pin "2") (pinfunction "K_2") (pintype "passive"))
      (node (ref "D148") (pin "2") (pinfunction "K_2") (pintype "passive"))
      (node (ref "D156") (pin "2") (pinfunction "K_2") (pintype "passive"))
      (node (ref "D164") (pin "2") (pinfunction "K_2") (pintype "passive"))
      (node (ref "P4") (pin "18") (pinfunction "18_18") (pintype "passive"))
    )
    (net (code "20") (name "/N1") (class "Default")
      (node (ref "P3") (pin "4") (pinfunction "4_4") (pintype "passive"))
    )
    (net (code "21") (name "/N2") (class "Default")
      (node (ref "P3") (pin "6") (pinfunction "6_6") (pintype "passive"))
    )
    (net (code "22") (name "/N3") (class "Default")
      (node (ref "P3") (pin "8") (pinfunction "8_8") (pintype "passive"))
    )
    (net (code "23") (name "/N4") (class "Default")
      (node (ref "P3") (pin "10") (pinfunction "10_10") (pintype "passive"))
    )
    (net (code "24") (name "/N5") (class "Default")
      (node (ref "P3") (pin "12") (pinfunction "12_12") (pintype "passive"))
    )
    (net (code "25") (name "/N6") (class "Default")
      (node (ref "P3") (pin "14") (pinfunction "14_14") (pintype "passive"))
    )
    (net (code "26") (name "/N7") (class "Default")
      (node (ref "P3") (pin "16") (pinfunction "16_16") (pintype "passive"))
    )
    (net (code "27") (name "/N8") (class "Default")
      (node (ref "P3") (pin "18") (pinfunction "18_18") (pintype "passive"))
    )
    (net (code "30") (name "/P1") (class "Default")
      (node (ref "P3") (pin "3") (pinfunction "3_3") (pintype "passive"))
    )
    (net (code "31") (name "/P2") (class "Default")
      (node (ref "P3") (pin "5") (pinfunction "5_5") (pintype "passive"))
    )
    (net (code "32") (name "/P3") (class "Default")
      (node (ref "P3") (pin "7") (pinfunction "7_7") (pintype "passive"))
    )
    (net (code "33") (name "/P4") (class "Default")
      (node (ref "P3") (pin "9") (pinfunction "9_9") (pintype "passive"))
    )
    (net (code "34") (name "/P5") (class "Default")
      (node (ref "P3") (pin "11") (pinfunction "11_11") (pintype "passive"))
    )
    (net (code "35") (name "/P6") (class "Default")
      (node (ref "P3") (pin "13") (pinfunction "13_13") (pintype "passive"))
    )
    (net (code "36") (name "/P7") (class "Default")
      (node (ref "P3") (pin "15") (pinfunction "15_15") (pintype "passive"))
    )
    (net (code "37") (name "/P8") (class "Default")
      (node (ref "P3") (pin "17") (pinfunction "17_17") (pintype "passive"))
    )
    (net (code "39") (name "/X1") (class "Default")
      (node (ref "P1") (pin "2") (pinfunction "2_2") (pintype "passive"))
    )
    (net (code "40") (name "/X2") (class "Default")
      (node (ref "P1") (pin "3") (pinfunction "3_3") (pintype "passive"))
    )
    (net (code "41") (name "/X3") (class "Default")
      (node (ref "P1") (pin "4") (pinfunction "4_4") (pintype "passive"))
    )
    (net (code "42") (name "/X4") (class "Default")
      (node (ref "P1") (pin "5") (pinfunction "5_5") (pintype "passive"))
    )
    (net (code "43") (name "/X5") (class "Default")
      (node (ref "P1") (pin "6") (pinfunction "6_6") (pintype "passive"))
    )
    (net (code "44") (name "/X6") (class "Default")
      (node (ref "P1") (pin "7") (pinfunction "7_7") (pintype "passive"))
    )
    (net (code "45") (name "/X7") (class "Default")
      (node (ref "P1") (pin "8") (pinfunction "8_8") (pintype "passive"))
    )
    (net (code "46") (name "/X8") (class "Default")
      (node (ref "P1") (pin "9") (pinfunction "9_9") (pintype "passive"))
    )
    (net (code "47") (name "/X9") (class "Default")
      (node (ref "P1") (pin "10") (pinfunction "10_10") (pintype "passive"))
    )
    (net (code "48") (name "/X10") (class "Default")
      (node (ref "P1") (pin "11") (pinfunction "11_11") (pintype "passive"))
    )
    (net (code "49") (name "/X11") (class "Default")
      (node (ref "P1") (pin "12") (pinfunction "12_12") (pintype "passive"))
    )
    (net (code "50") (name "/X12") (class "Default")
      (node (ref "P1") (pin "13") (pinfunction "13_13") (pintype "passive"))
    )
    (net (code "51") (name "/X13") (class "Default")
      (node (ref "P1") (pin "14") (pinfunction "14_14") (pintype "passive"))
    )
    (net (code "52") (name "/X14") (class "Default")
      (node (ref "P1") (pin "15") (pinfunction "15_15") (pintype "passive"))
    )
    (net (code "53") (name "/X15") (class "Default")
      (node (ref "P1") (pin "16") (pinfunction "16_16") (pintype "passive"))
    )
    (net (code "54") (name "/X16") (class "Default")
      (node (ref "P1") (pin "17") (pinfunction "17_17") (pintype "passive"))
    )
    (net (code "57") (name "/Y1") (class "Default")
      (node (ref "P2") (pin "2") (pinfunction "2_2") (pintype "passive"))
    )
    (net (code "58") (name "/Y2") (class "Default")
      (node (ref "P2") (pin "3") (pinfunction "3_3") (pintype "passive"))
    )
    (net (code "59") (name "/Y3") (class "Default")
      (node (ref "P2") (pin "4") (pinfunction "4_4") (pintype "passive"))
    )
    (net (code "60") (name "/Y4") (class "Default")
      (node (ref "P2") (pin "5") (pinfunction "5_5") (pintype "passive"))
    )
    (net (code "61") (name "/Y5") (class "Default")
      (node (ref "P2") (pin "6") (pinfunction "6_6") (pintype "passive"))
    )
    (net (code "62") (name "/Y6") (class "Default")
      (node (ref "P2") (pin "7") (pinfunction "7_7") (pintype "passive"))
    )
    (net (code "63") (name "/Y7") (class "Default")
      (node (ref "P2") (pin "8") (pinfunction "8_8") (pintype "passive"))
    )
    (net (code "64") (name "/Y8") (class "Default")
      (node (ref "P2") (pin "9") (pinfunction "9_9") (pintype "passive"))
    )
    (net (code "66") (name "Net-(D101-A)") (class "Default")
      (node (ref "D101") (pin "1") (pinfunction "A_1") (pintype "passive"))
      (node (ref "L1") (pin "1") (pinfunction "1_1") (pintype "passive"))
    )
    (net (code "67") (name "Net-(D102-A)") (class "Default")
      (node (ref "D102") (pin "1") (pinfunction "A_1") (pintype "passive"))
      (node (ref "L2") (pin "1") (pinfunction "1_1") (pintype "passive"))
    )
    (net (code "68") (name "Net-(D103-A)") (class "Default")
      (node (ref "D103") (pin "1") (pinfunction "A_1") (pintype "passive"))
      (node (ref "L3") (pin "1") (pinfunction "1_1") (pintype "passive"))
    )
    (net (code "69") (name "Net-(D104-A)") (class "Default")
      (node (ref "D104") (pin "1") (pinfunction "A_1") (pintype "passive"))
      (node (ref "L4") (pin "1") (pinfunction "1_1") (pintype "passive"))
    )
    (net (code "70") (name "Net-(D105-A)") (class "Default")
      (node (ref "D105") (pin "1") (pinfunction "A_1") (pintype "passive"))
      (node (ref "L5") (pin "1") (pinfunction "1_1") (pintype "passive"))
    )
    (net (code "71") (name "Net-(D106-A)") (class "Default")
      (node (ref "D106") (pin "1") (pinfunction "A_1") (pintype "passive"))
      (node (ref "L6") (pin "1") (pinfunction "1_1") (pintype "passive"))
    )
    (net (code "72") (name "Net-(D107-A)") (class "Default")
      (node (ref "D107") (pin "1") (pinfunction "A_1") (pintype "passive"))
      (node (ref "L7") (pin "1") (pinfunction "1_1") (pintype "passive"))
    )
    (net (code "73") (name "Net-(D108-A)") (class "Default")
      (node (ref "D108") (pin "1") (pinfunction "A_1") (pintype "passive"))
      (node (ref "L8") (pin "1") (pinfunction "1_1") (pintype "passive"))
    )
    (net (code "74") (name "Net-(D109-A)") (class "Default")
      (node (ref "D109") (pin "1") (pinfunction "A_1") (pintype "passive"))
      (node (ref "L9") (pin "1") (pinfunction "1_1") (pintype "passive"))
    )
    (net (code "75") (name "Net-(D110-A)") (class "Default")
      (node (ref "D110") (pin "1") (pinfunction "A_1") (pintype "passive"))
      (node (ref "L10") (pin "1") (pinfunction "1_1") (pintype "passive"))
    )
    (net (code "76") (name "Net-(D111-A)") (class "Default")
      (node (ref "D111") (pin "1") (pinfunction "A_1") (pintype "passive"))
      (node (ref "L11") (pin "1") (pinfunction "1_1") (pintype "passive"))
    )
    (net (code "77") (name "Net-(D112-A)") (class "Default")
      (node (ref "D112") (pin "1") (pinfunction "A_1") (pintype "passive"))
      (node (ref "L12") (pin "1") (pinfunction "1_1") (pintype "passive"))
    )
    (net (code "78") (name "Net-(D113-A)") (class "Default")
      (node (ref "D113") (pin "1") (pinfunction "A_1") (pintype "passive"))
      (node (ref "L13") (pin "1") (pinfunction "1_1") (pintype "passive"))
    )
    (net (code "79") (name "Net-(D114-A)") (class "Default")
      (node (ref "D114") (pin "1") (pinfunction "A_1") (pintype "passive"))
      (node (ref "L14") (pin "1") (pinfunction "1_1") (pintype "passive"))
    )
    (net (code "80") (name "Net-(D115-A)") (class "Default")
      (node (ref "D115") (pin "1") (pinfunction "A_1") (pintype "passive"))
      (node (ref "L15") (pin "1") (pinfunction "1_1") (pintype "passive"))
    )
    (net (code "81") (name "Net-(D116-A)") (class "Default")
      (node (ref "D116") (pin "1") (pinfunction "A_1") (pintype "passive"))
      (node (ref "L16") (pin "1") (pinfunction "1_1") (pintype "passive"))
    )
    (net (code "82") (name "Net-(D117-A)") (class "Default")
      (node (ref "D117") (pin "1") (pinfunction "A_1") (pintype "passive"))
      (node (ref "L17") (pin "1") (pinfunction "1_1") (pintype "passive"))
    )
    (net (code "83") (name "Net-(D118-A)") (class "Default")
      (node (ref "D118") (pin "1") (pinfunction "A_1") (pintype "passive"))
      (node (ref "L18") (pin "1") (pinfunction "1_1") (pintype "passive"))
    )
    (net (code "84") (name "Net-(D119-A)") (class "Default")
      (node (ref "D119") (pin "1") (pinfunction "A_1") (pintype "passive"))
      (node (ref "L19") (pin "1") (pinfunction "1_1") (pintype "passive"))
    )
    (net (code "85") (name "Net-(D120-A)") (class "Default")
      (node (ref "D120") (pin "1") (pinfunction "A_1") (pintype "passive"))
      (node (ref "L20") (pin "1") (pinfunction "1_1") (pintype "passive"))
    )
    (net (code "86") (name "Net-(D121-A)") (class "Default")
      (node (ref "D121") (pin "1") (pinfunction "A_1") (pintype "passive"))
      (node (ref "L21") (pin "1") (pinfunction "1_1") (pintype "passive"))
    )
    (net (code "87") (name "Net-(D122-A)") (class "Default")
      (node (ref "D122") (pin "1") (pinfunction "A_1") (pintype "passive"))
      (node (ref "L22") (pin "1") (pinfunction "1_1") (pintype "passive"))
    )
    (net (code "88") (name "Net-(D123-A)") (class "Default")
      (node (ref "D123") (pin "1") (pinfunction "A_1") (pintype "passive"))
      (node (ref "L23") (pin "1") (pinfunction "1_1") (pintype "passive"))
    )
    (net (code "89") (name "Net-(D124-A)") (class "Default")
      (node (ref "D124") (pin "1") (pinfunction "A_1") (pintype "passive"))
      (node (ref "L24") (pin "1") (pinfunction "1_1") (pintype "passive"))
    )
    (net (code "90") (name "Net-(D125-A)") (class "Default")
      (node (ref "D125") (pin "1") (pinfunction "A_1") (pintype "passive"))
      (node (ref "L25") (pin "1") (pinfunction "1_1") (pintype "passive"))
    )
    (net (code "91") (name "Net-(D126-A)") (class "Default")
      (node (ref "D126") (pin "1") (pinfunction "A_1") (pintype "passive"))
      (node (ref "L26") (pin "1") (pinfunction "1_1") (pintype "passive"))
    )
    (net (code "92") (name "Net-(D127-A)") (class "Default")
      (node (ref "D127") (pin "1") (pinfunction "A_1") (pintype "passive"))
      (node (ref "L27") (pin "1") (pinfunction "1_1") (pintype "passive"))
    )
    (net (code "93") (name "Net-(D128-A)") (class "Default")
      (node (ref "D128") (pin "1") (pinfunction "A_1") (pintype "passive"))
      (node (ref "L28") (pin "1") (pinfunction "1_1") (pintype "passive"))
    )
    (net (code "94") (name "Net-(D129-A)") (class "Default")
      (node (ref "D129") (pin "1") (pinfunction "A_1") (pintype "passive"))
      (node (ref "L29") (pin "1") (pinfunction "1_1") (pintype "passive"))
    )
    (net (code "95") (name "Net-(D130-A)") (class "Default")
      (node (ref "D130") (pin "1") (pinfunction "A_1") (pintype "passive"))
      (node (ref "L30") (pin "1") (pinfunction "1_1") (pintype "passive"))
    )
    (net (code "96") (name "Net-(D131-A)") (class "Default")
      (node (ref "D131") (pin "1") (pinfunction "A_1") (pintype "passive"))
      (node (ref "L31") (pin "1") (pinfunction "1_1") (pintype "passive"))
    )
    (net (code "97") (name "Net-(D132-A)") (class "Default")
      (node (ref "D132") (pin "1") (pinfunction "A_1") (pintype "passive"))
      (node (ref "L32") (pin "1") (pinfunction "1_1") (pintype "passive"))
    )
    (net (code "98") (name "Net-(D133-A)") (class "Default")
      (node (ref "D133") (pin "1") (pinfunction "A_1") (pintype "passive"))
      (node (ref "L33") (pin "1") (pinfunction "1_1") (pintype "passive"))
    )
    (net (code "99") (name "Net-(D134-A)") (class "Default")
      (node (ref "D134") (pin "1") (pinfunction "A_1") (pintype "passive"))
      (node (ref "L34") (pin "1") (pinfunction "1_1") (pintype "passive"))
    )
    (net (code "100") (name "Net-(D135-A)") (class "Default")
      (node (ref "D135") (pin "1") (pinfunction "A_1") (pintype "passive"))
      (node (ref "L35") (pin "1") (pinfunction "1_1") (pintype "passive"))
    )
    (net (code "101") (name "Net-(D136-A)") (class "Default")
      (node (ref "D136") (pin "1") (pinfunction "A_1") (pintype "passive"))
      (node (ref "L36") (pin "1") (pinfunction "1_1") (pintype "passive"))
    )
    (net (code "102") (name "Net-(D137-A)") (class "Default")
      (node (ref "D137") (pin "1") (pinfunction "A_1") (pintype "passive"))
      (node (ref "L37") (pin "1") (pinfunction "1_1") (pintype "passive"))
    )
    (net (code "103") (name "Net-(D138-A)") (class "Default")
      (node (ref "D138") (pin "1") (pinfunction "A_1") (pintype "passive"))
      (node (ref "L38") (pin "1") (pinfunction "1_1") (pintype "passive"))
    )
    (net (code "104") (name "Net-(D139-A)") (class "Default")
      (node (ref "D139") (pin "1") (pinfunction "A_1") (pintype "passive"))
      (node (ref "L39") (pin "1") (pinfunction "1_1") (pintype "passive"))
    )
    (net (code "105") (name "Net-(D140-A)") (class "Default")
      (node (ref "D140") (pin "1") (pinfunction "A_1") (pintype "passive"))
      (node (ref "L40") (pin "1") (pinfunction "1_1") (pintype "passive"))
    )
    (net (code "106") (name "Net-(D141-A)") (class "Default")
      (node (ref "D141") (pin "1") (pinfunction "A_1") (pintype "passive"))
      (node (ref "L41") (pin "1") (pinfunction "1_1") (pintype "passive"))
    )
    (net (code "107") (name "Net-(D142-A)") (class "Default")
      (node (ref "D142") (pin "1") (pinfunction "A_1") (pintype "passive"))
      (node (ref "L42") (pin "1") (pinfunction "1_1") (pintype "passive"))
    )
    (net (code "108") (name "Net-(D143-A)") (class "Default")
      (node (ref "D143") (pin "1") (pinfunction "A_1") (pintype "passive"))
      (node (ref "L43") (pin "1") (pinfunction "1_1") (pintype "passive"))
    )
    (net (code "109") (name "Net-(D144-A)") (class "Default")
      (node (ref "D144") (pin "1") (pinfunction "A_1") (pintype "passive"))
      (node (ref "L44") (pin "1") (pinfunction "1_1") (pintype "passive"))
    )
    (net (code "110") (name "Net-(D145-A)") (class "Default")
      (node (ref "D145") (pin "1") (pinfunction "A_1") (pintype "passive"))
      (node (ref "L45") (pin "1") (pinfunction "1_1") (pintype "passive"))
    )
    (net (code "111") (name "Net-(D146-A)") (class "Default")
      (node (ref "D146") (pin "1") (pinfunction "A_1") (pintype "passive"))
      (node (ref "L46") (pin "1") (pinfunction "1_1") (pintype "passive"))
    )
    (net (code "112") (name "Net-(D147-A)") (class "Default")
      (node (ref "D147") (pin "1") (pinfunction "A_1") (pintype "passive"))
      (node (ref "L47") (pin "1") (pinfunction "1_1") (pintype "passive"))
    )
    (net (code "113") (name "Net-(D148-A)") (class "Default")
      (node (ref "D148") (pin "1") (pinfunction "A_1") (pintype "passive"))
      (node (ref "L48") (pin "1") (pinfunction "1_1") (pintype "passive"))
    )
    (net (code "114") (name "Net-(D149-A)") (class "Default")
      (node (ref "D149") (pin "1") (pinfunction "A_1") (pintype "passive"))
      (node (ref "L49") (pin "1") (pinfunction "1_1") (pintype "passive"))
    )
    (net (code "115") (name "Net-(D150-A)") (class "Default")
      (node (ref "D150") (pin "1") (pinfunction "A_1") (pintype "passive"))
      (node (ref "L50") (pin "1") (pinfunction "1_1") (pintype "passive"))
    )
    (net (code "116") (name "Net-(D151-A)") (class "Default")
      (node (ref "D151") (pin "1") (pinfunction "A_1") (pintype "passive"))
      (node (ref "L51") (pin "1") (pinfunction "1_1") (pintype "passive"))
    )
    (net (code "117") (name "Net-(D152-A)") (class "Default")
      (node (ref "D152") (pin "1") (pinfunction "A_1") (pintype "passive"))
      (node (ref "L52") (pin "1") (pinfunction "1_1") (pintype "passive"))
    )
    (net (code "118") (name "Net-(D153-A)") (class "Default")
      (node (ref "D153") (pin "1") (pinfunction "A_1") (pintype "passive"))
      (node (ref "L53") (pin "1") (pinfunction "1_1") (pintype "passive"))
    )
    (net (code "119") (name "Net-(D154-A)") (class "Default")
      (node (ref "D154") (pin "1") (pinfunction "A_1") (pintype "passive"))
      (node (ref "L54") (pin "1") (pinfunction "1_1") (pintype "passive"))
    )
    (net (code "120") (name "Net-(D155-A)") (class "Default")
      (node (ref "D155") (pin "1") (pinfunction "A_1") (pintype "passive"))
      (node (ref "L55") (pin "1") (pinfunction "1_1") (pintype "passive"))
    )
    (net (code "121") (name "Net-(D156-A)") (class "Default")
      (node (ref "D156") (pin "1") (pinfunction "A_1") (pintype "passive"))
      (node (ref "L56") (pin "1") (pinfunction "1_1") (pintype "passive"))
    )
    (net (code "122") (name "Net-(D157-A)") (class "Default")
      (node (ref "D157") (pin "1") (pinfunction "A_1") (pintype "passive"))
      (node (ref "L57") (pin "1") (pinfunction "1_1") (pintype "passive"))
    )
    (net (code "123") (name "Net-(D158-A)") (class "Default")
      (node (ref "D158") (pin "1") (pinfunction "A_1") (pintype "passive"))
      (node (ref "L58") (pin "1") (pinfunction "1_1") (pintype "passive"))
    )
    (net (code "124") (name "Net-(D159-A)") (class "Default")
      (node (ref "D159") (pin "1") (pinfunction "A_1") (pintype "passive"))
      (node (ref "L59") (pin "1") (pinfunction "1_1") (pintype "passive"))
    )
    (net (code "125") (name "Net-(D160-A)") (class "Default")
      (node (ref "D160") (pin "1") (pinfunction "A_1") (pintype "passive"))
      (node (ref "L60") (pin "1") (pinfunction "1_1") (pintype "passive"))
    )
    (net (code "126") (name "Net-(D161-A)") (class "Default")
      (node (ref "D161") (pin "1") (pinfunction "A_1") (pintype "passive"))
      (node (ref "L61") (pin "1") (pinfunction "1_1") (pintype "passive"))
    )
    (net (code "127") (name "Net-(D162-A)") (class "Default")
      (node (ref "D162") (pin "1") (pinfunction "A_1") (pintype "passive"))
      (node (ref "L62") (pin "1") (pinfunction "1_1") (pintype "passive"))
    )
    (net (code "128") (name "Net-(D163-A)") (class "Default")
      (node (ref "D163") (pin "1") (pinfunction "A_1") (pintype "passive"))
      (node (ref "L63") (pin "1") (pinfunction "1_1") (pintype "passive"))
    )
    (net (code "129") (name "Net-(D164-A)") (class "Default")
      (node (ref "D164") (pin "1") (pinfunction "A_1") (pintype "passive"))
      (node (ref "L64") (pin "1") (pinfunction "1_1") (pintype "passive"))
    )
    (net (code "130") (name "unconnected-(P1-Pad1)") (class "Default")
      (node (ref "P1") (pin "1") (pinfunction "1_1") (pintype "passive"))
    )
    (net (code "131") (name "unconnected-(P1-Pad18)") (class "Default")
      (node (ref "P1") (pin "18") (pinfunction "18_18") (pintype "passive"))
    )
    (net (code "132") (name "unconnected-(P2-Pad1)") (class "Default")
      (node (ref "P2") (pin "1") (pinfunction "1_1") (pintype "passive"))
    )
    (net (code "133") (name "unconnected-(P2-Pad10)") (class "Default")
      (node (ref "P2") (pin "10") (pinfunction "10_10") (pintype "passive"))
    )
    (net (code "134") (name "unconnected-(P3-Pad1)") (class "Default")
      (node (ref "P3") (pin "1") (pinfunction "1_1") (pintype "passive"))
    )
    (net (code "135") (name "unconnected-(P3-Pad2)") (class "Default")
      (node (ref "P3") (pin "2") (pinfunction "2_2") (pintype "passive"))
    )
    (net (code "136") (name "unconnected-(P3-Pad19)") (class "Default")
      (node (ref "P3") (pin "19") (pinfunction "19_19") (pintype "passive"))
    )
    (net (code "137") (name "unconnected-(P3-Pad20)") (class "Default")
      (node (ref "P3") (pin "20") (pinfunction "20_20") (pintype "passive"))
    )
    (net (code "138") (name "unconnected-(P4-Pad1)") (class "Default")
      (node (ref "P4") (pin "1") (pinfunction "1_1") (pintype "passive"))
    )
    (net (code "139") (name "unconnected-(P4-Pad2)") (class "Default")
      (node (ref "P4") (pin "2") (pinfunction "2_2") (pintype "passive"))
    )
    (net (code "140") (name "unconnected-(P4-Pad19)") (class "Default")
      (node (ref "P4") (pin "19") (pinfunction "19_19") (pintype "passive"))
    )
    (net (code "141") (name "unconnected-(P4-Pad20)") (class "Default")
      (node (ref "P4") (pin "20") (pinfunction "20_20") (pintype "passive"))
    )
  )
)
